# Rariot.net
KiCad netlist of a schematic drawn in EAGLE
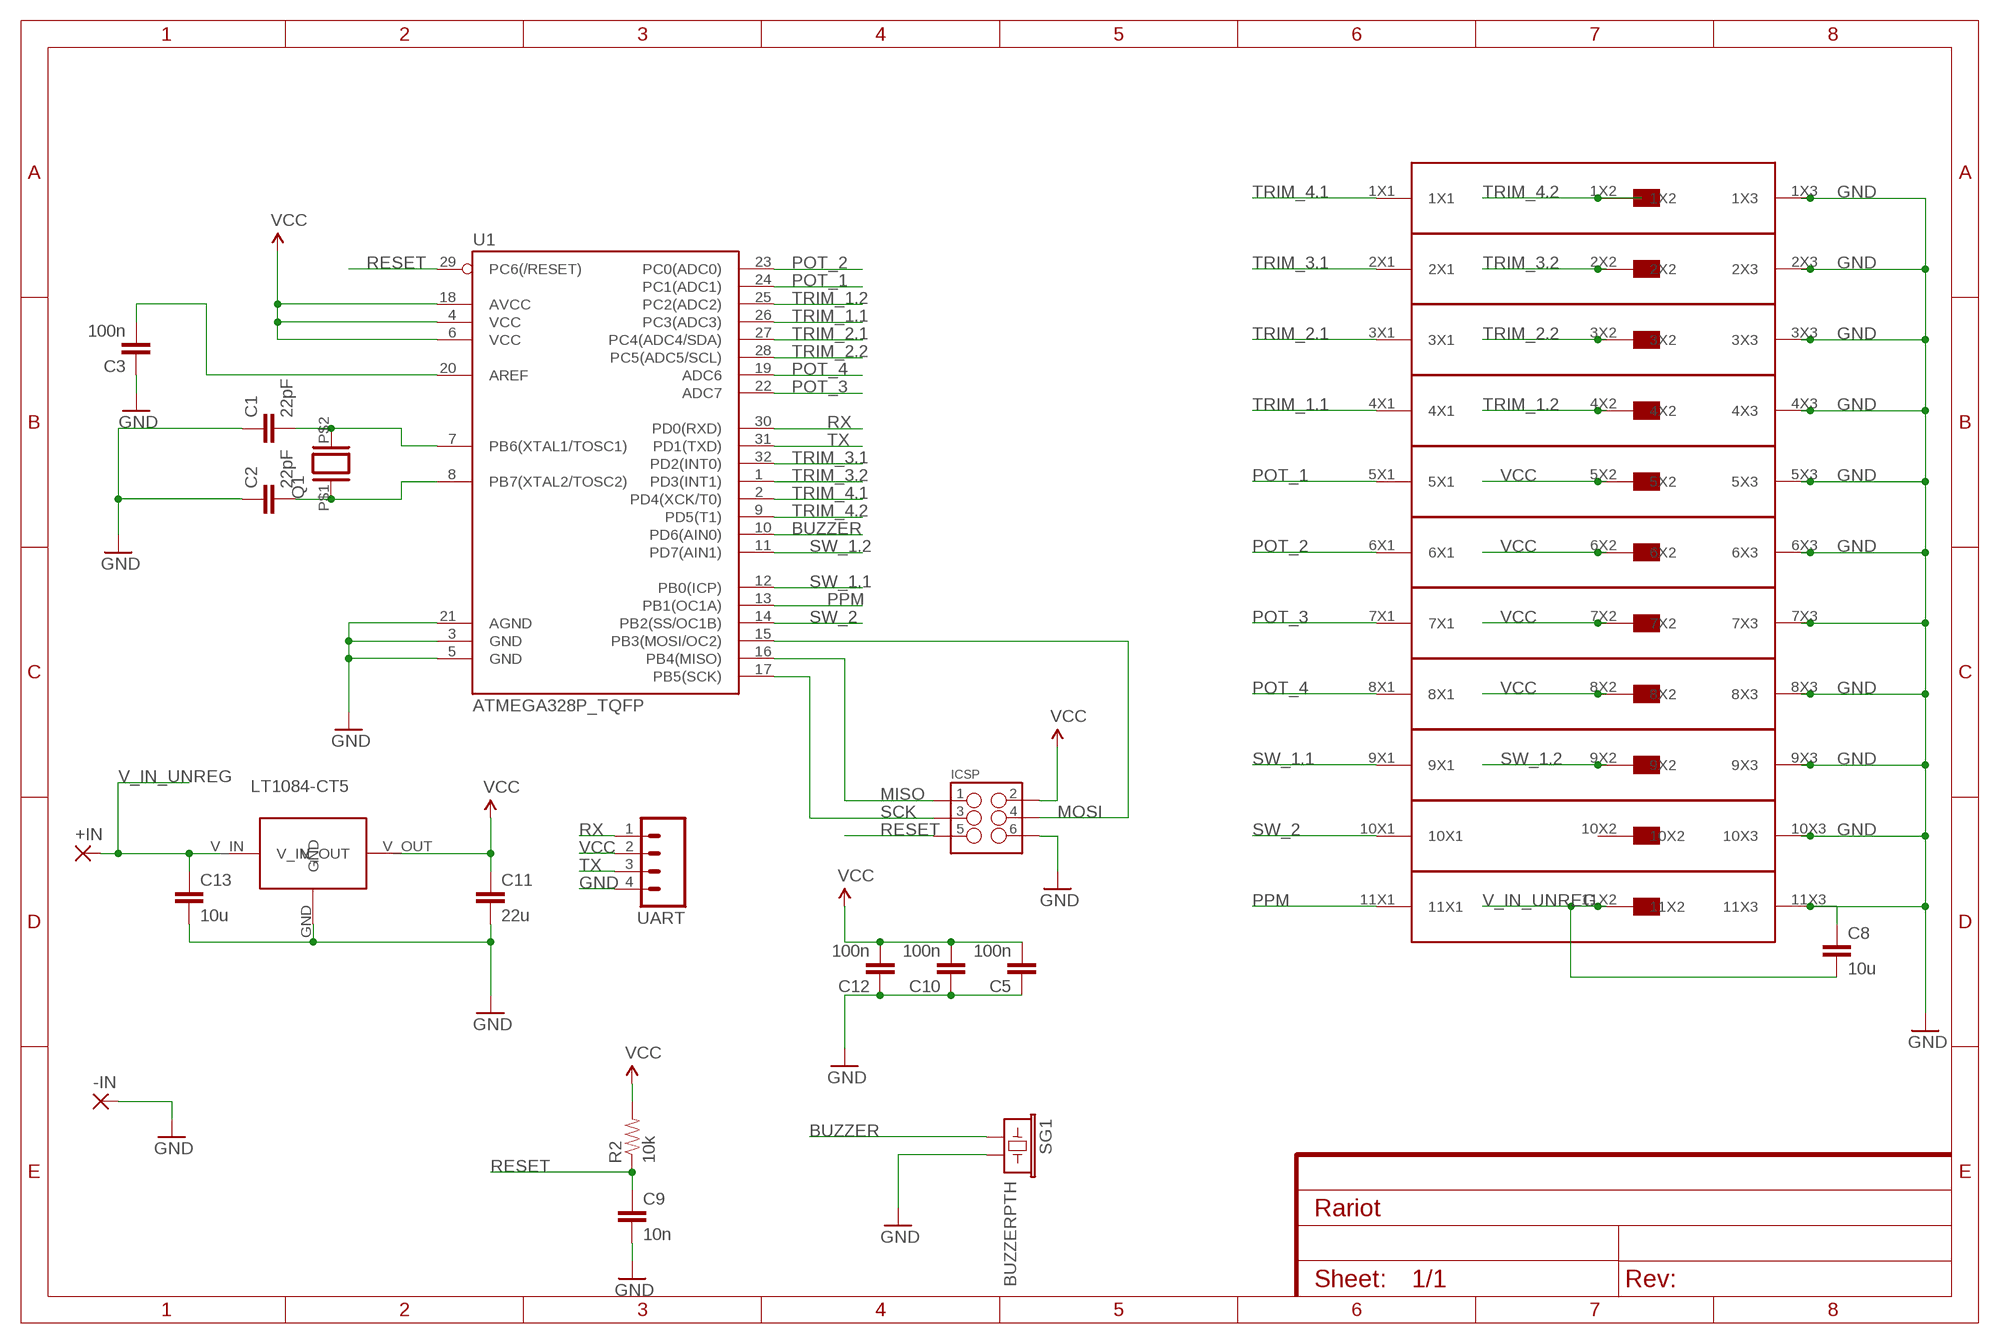
[diagram p0: schematic, sheet 1]

(export (version "E")
  (design (tool "Eeschema 10.0.6"))
  (components
    (comp (ref "+IN")
      (value "SMD5")
      (footprint "eagle-import:SMD2,54-5,08")
      (libsource (lib "eagle-import") (part "SMD5"))
    )
    (comp (ref "-IN")
      (value "SMD5")
      (footprint "eagle-import:SMD2,54-5,08")
      (libsource (lib "eagle-import") (part "SMD5"))
    )
    (comp (ref "C1")
      (value "22pF")
      (footprint "eagle-import:0805")
      (libsource (lib "eagle-import") (part "CAP0805"))
    )
    (comp (ref "C2")
      (value "22pF")
      (footprint "eagle-import:0805")
      (libsource (lib "eagle-import") (part "CAP0805"))
    )
    (comp (ref "C3")
      (value "100n")
      (footprint "eagle-import:0805")
      (libsource (lib "eagle-import") (part "CAP0805"))
    )
    (comp (ref "C5")
      (value "100n")
      (footprint "eagle-import:0805")
      (libsource (lib "eagle-import") (part "CAP0805"))
    )
    (comp (ref "C8")
      (value "10u")
      (footprint "eagle-import:1206")
      (libsource (lib "eagle-import") (part "CAP1206"))
    )
    (comp (ref "C9")
      (value "10n")
      (footprint "eagle-import:0805")
      (libsource (lib "eagle-import") (part "CAP0805"))
    )
    (comp (ref "C10")
      (value "100n")
      (footprint "eagle-import:0805")
      (libsource (lib "eagle-import") (part "CAP0805"))
    )
    (comp (ref "C11")
      (value "22u")
      (footprint "eagle-import:1206")
      (libsource (lib "eagle-import") (part "CAP1206"))
    )
    (comp (ref "C12")
      (value "100n")
      (footprint "eagle-import:0805")
      (libsource (lib "eagle-import") (part "CAP0805"))
    )
    (comp (ref "C13")
      (value "10u")
      (footprint "eagle-import:1206")
      (libsource (lib "eagle-import") (part "CAP1206"))
    )
    (comp (ref "ICSP")
      (value "FEMALE 2x3")
      (footprint "eagle-import:2X3")
      (libsource (lib "eagle-import") (part "M03X2FEMALE"))
    )
    (comp (ref "Q1")
      (value "XTAL/SSMD")
      (footprint "eagle-import:X-TAL_SMD")
      (libsource (lib "eagle-import") (part "XTAL/SSMD"))
    )
    (comp (ref "R2")
      (value "10k")
      (footprint "eagle-import:0805")
      (libsource (lib "eagle-import") (part "RESISTOR0805-RES"))
    )
    (comp (ref "SG1")
      (value "BUZZERPTH")
      (footprint "eagle-import:BUZZER-12MM")
      (libsource (lib "eagle-import") (part "BUZZERPTH"))
    )
    (comp (ref "U$1")
      (value "11X3_2.54_PIN_HEADER")
      (footprint "eagle-import:11X3_2,54_PIN_HEADER")
      (libsource (lib "eagle-import") (part "11X3_2.54_PIN_HEADER"))
    )
    (comp (ref "U$2")
      (value "LT1084-CT5")
      (footprint "eagle-import:TO-220")
      (libsource (lib "eagle-import") (part "LT1084-CT5"))
    )
    (comp (ref "U1")
      (value "ATMEGA328P_TQFP")
      (footprint "eagle-import:TQFP32-08")
      (libsource (lib "eagle-import") (part "ATMEGA328P_TQFP"))
    )
    (comp (ref "UART")
      (value "M04PTH")
      (footprint "eagle-import:1X04")
      (libsource (lib "eagle-import") (part "M04PTH"))
    )
  )
  (nets
    (net (code "1") (name "/BUZZER") (class "Default")
      (node (ref "SG1") (pin "+") (pinfunction "1_+") (pintype "passive"))
      (node (ref "U1") (pin "10") (pinfunction "PD6(AIN0)_10") (pintype "bidirectional"))
    )
    (net (code "2") (name "/MISO") (class "Default")
      (node (ref "ICSP") (pin "1") (pinfunction "1_1") (pintype "bidirectional"))
      (node (ref "U1") (pin "16") (pinfunction "PB4(MISO)_16") (pintype "bidirectional"))
    )
    (net (code "3") (name "/MOSI") (class "Default")
      (node (ref "ICSP") (pin "4") (pinfunction "4_4") (pintype "bidirectional"))
      (node (ref "U1") (pin "15") (pinfunction "PB3(MOSI/OC2)_15") (pintype "bidirectional"))
    )
    (net (code "4") (name "/POT_1") (class "Default")
      (node (ref "U$1") (pin "5X1") (pinfunction "5X1_5X1") (pintype "bidirectional"))
      (node (ref "U1") (pin "24") (pinfunction "PC1(ADC1)_24") (pintype "bidirectional"))
    )
    (net (code "5") (name "/POT_2") (class "Default")
      (node (ref "U$1") (pin "6X1") (pinfunction "6X1_6X1") (pintype "bidirectional"))
      (node (ref "U1") (pin "23") (pinfunction "PC0(ADC0)_23") (pintype "bidirectional"))
    )
    (net (code "6") (name "/POT_3") (class "Default")
      (node (ref "U$1") (pin "7X1") (pinfunction "7X1_7X1") (pintype "bidirectional"))
      (node (ref "U1") (pin "22") (pinfunction "ADC7_22") (pintype "bidirectional"))
    )
    (net (code "7") (name "/POT_4") (class "Default")
      (node (ref "U$1") (pin "8X1") (pinfunction "8X1_8X1") (pintype "bidirectional"))
      (node (ref "U1") (pin "19") (pinfunction "ADC6_19") (pintype "bidirectional"))
    )
    (net (code "8") (name "/PPM") (class "Default")
      (node (ref "U$1") (pin "11X1") (pinfunction "11X1_11X1") (pintype "bidirectional"))
      (node (ref "U1") (pin "13") (pinfunction "PB1(OC1A)_13") (pintype "bidirectional"))
    )
    (net (code "9") (name "/RESET") (class "Default")
      (node (ref "C9") (pin "1") (pinfunction "1_1") (pintype "passive"))
      (node (ref "ICSP") (pin "5") (pinfunction "5_5") (pintype "bidirectional"))
      (node (ref "R2") (pin "1") (pinfunction "1_1") (pintype "passive"))
      (node (ref "U1") (pin "29") (pinfunction "PC6(/RESET)_29") (pintype "bidirectional"))
    )
    (net (code "10") (name "/RX") (class "Default")
      (node (ref "U1") (pin "30") (pinfunction "PD0(RXD)_30") (pintype "bidirectional"))
      (node (ref "UART") (pin "1") (pinfunction "1_1") (pintype "passive"))
    )
    (net (code "11") (name "/SCK") (class "Default")
      (node (ref "ICSP") (pin "3") (pinfunction "3_3") (pintype "bidirectional"))
      (node (ref "U1") (pin "17") (pinfunction "PB5(SCK)_17") (pintype "bidirectional"))
    )
    (net (code "12") (name "/SW_1.1") (class "Default")
      (node (ref "U$1") (pin "9X1") (pinfunction "9X1_9X1") (pintype "bidirectional"))
      (node (ref "U1") (pin "12") (pinfunction "PB0(ICP)_12") (pintype "bidirectional"))
    )
    (net (code "13") (name "/SW_1.2") (class "Default")
      (node (ref "U$1") (pin "9X2") (pinfunction "9X2_9X2") (pintype "bidirectional"))
      (node (ref "U1") (pin "11") (pinfunction "PD7(AIN1)_11") (pintype "bidirectional"))
    )
    (net (code "14") (name "/SW_2") (class "Default")
      (node (ref "U$1") (pin "10X1") (pinfunction "10X1_10X1") (pintype "bidirectional"))
      (node (ref "U1") (pin "14") (pinfunction "PB2(SS/OC1B)_14") (pintype "bidirectional"))
    )
    (net (code "15") (name "/TRIM_1.1") (class "Default")
      (node (ref "U$1") (pin "4X1") (pinfunction "4X1_4X1") (pintype "bidirectional"))
      (node (ref "U1") (pin "26") (pinfunction "PC3(ADC3)_26") (pintype "bidirectional"))
    )
    (net (code "16") (name "/TRIM_1.2") (class "Default")
      (node (ref "U$1") (pin "4X2") (pinfunction "4X2_4X2") (pintype "bidirectional"))
      (node (ref "U1") (pin "25") (pinfunction "PC2(ADC2)_25") (pintype "bidirectional"))
    )
    (net (code "17") (name "/TRIM_2.1") (class "Default")
      (node (ref "U$1") (pin "3X1") (pinfunction "3X1_3X1") (pintype "bidirectional"))
      (node (ref "U1") (pin "27") (pinfunction "PC4(ADC4/SDA)_27") (pintype "bidirectional"))
    )
    (net (code "18") (name "/TRIM_2.2") (class "Default")
      (node (ref "U$1") (pin "3X2") (pinfunction "3X2_3X2") (pintype "bidirectional"))
      (node (ref "U1") (pin "28") (pinfunction "PC5(ADC5/SCL)_28") (pintype "bidirectional"))
    )
    (net (code "19") (name "/TRIM_3.1") (class "Default")
      (node (ref "U$1") (pin "2X1") (pinfunction "2X1_2X1") (pintype "bidirectional"))
      (node (ref "U1") (pin "32") (pinfunction "PD2(INT0)_32") (pintype "bidirectional"))
    )
    (net (code "20") (name "/TRIM_3.2") (class "Default")
      (node (ref "U$1") (pin "2X2") (pinfunction "2X2_2X2") (pintype "bidirectional"))
      (node (ref "U1") (pin "1") (pinfunction "PD3(INT1)_1") (pintype "bidirectional"))
    )
    (net (code "21") (name "/TRIM_4.1") (class "Default")
      (node (ref "U$1") (pin "1X1") (pinfunction "1X1_1X1") (pintype "bidirectional"))
      (node (ref "U1") (pin "2") (pinfunction "PD4(XCK/T0)_2") (pintype "bidirectional"))
    )
    (net (code "22") (name "/TRIM_4.2") (class "Default")
      (node (ref "U$1") (pin "1X2") (pinfunction "1X2_1X2") (pintype "bidirectional"))
      (node (ref "U1") (pin "9") (pinfunction "PD5(T1)_9") (pintype "bidirectional"))
    )
    (net (code "23") (name "/TX") (class "Default")
      (node (ref "U1") (pin "31") (pinfunction "PD1(TXD)_31") (pintype "bidirectional"))
      (node (ref "UART") (pin "3") (pinfunction "3_3") (pintype "passive"))
    )
    (net (code "24") (name "/V_IN_UNREG") (class "Default")
      (node (ref "+IN") (pin "1") (pinfunction "P_1") (pintype "passive"))
      (node (ref "C13") (pin "1") (pinfunction "1_1") (pintype "passive"))
      (node (ref "C8") (pin "2") (pinfunction "2_2") (pintype "passive"))
      (node (ref "U$1") (pin "11X2") (pinfunction "11X2_11X2") (pintype "bidirectional"))
      (node (ref "U$2") (pin "V_IN") (pinfunction "V_IN_V_IN") (pintype "bidirectional"))
    )
    (net (code "25") (name "GND") (class "Default")
      (node (ref "-IN") (pin "1") (pinfunction "P_1") (pintype "passive"))
      (node (ref "C1") (pin "1") (pinfunction "1_1") (pintype "passive"))
      (node (ref "C10") (pin "1") (pinfunction "1_1") (pintype "passive"))
      (node (ref "C11") (pin "2") (pinfunction "2_2") (pintype "passive"))
      (node (ref "C12") (pin "1") (pinfunction "1_1") (pintype "passive"))
      (node (ref "C13") (pin "2") (pinfunction "2_2") (pintype "passive"))
      (node (ref "C2") (pin "1") (pinfunction "1_1") (pintype "passive"))
      (node (ref "C3") (pin "1") (pinfunction "1_1") (pintype "passive"))
      (node (ref "C5") (pin "1") (pinfunction "1_1") (pintype "passive"))
      (node (ref "C8") (pin "1") (pinfunction "1_1") (pintype "passive"))
      (node (ref "C9") (pin "2") (pinfunction "2_2") (pintype "passive"))
      (node (ref "ICSP") (pin "6") (pinfunction "6_6") (pintype "bidirectional"))
      (node (ref "SG1") (pin "-") (pinfunction "2_-") (pintype "passive"))
      (node (ref "U$1") (pin "10X3") (pinfunction "10X3_10X3") (pintype "bidirectional"))
      (node (ref "U$1") (pin "11X3") (pinfunction "11X3_11X3") (pintype "bidirectional"))
      (node (ref "U$1") (pin "1X3") (pinfunction "1X3_1X3") (pintype "bidirectional"))
      (node (ref "U$1") (pin "2X3") (pinfunction "2X3_2X3") (pintype "bidirectional"))
      (node (ref "U$1") (pin "3X3") (pinfunction "3X3_3X3") (pintype "bidirectional"))
      (node (ref "U$1") (pin "4X3") (pinfunction "4X3_4X3") (pintype "bidirectional"))
      (node (ref "U$1") (pin "5X3") (pinfunction "5X3_5X3") (pintype "bidirectional"))
      (node (ref "U$1") (pin "6X3") (pinfunction "6X3_6X3") (pintype "bidirectional"))
      (node (ref "U$1") (pin "7X3") (pinfunction "7X3_7X3") (pintype "bidirectional"))
      (node (ref "U$1") (pin "8X3") (pinfunction "8X3_8X3") (pintype "bidirectional"))
      (node (ref "U$1") (pin "9X3") (pinfunction "9X3_9X3") (pintype "bidirectional"))
      (node (ref "U$2") (pin "GND") (pinfunction "GND_GND") (pintype "bidirectional"))
      (node (ref "U1") (pin "21") (pinfunction "AGND_21") (pintype "bidirectional"))
      (node (ref "U1") (pin "3") (pinfunction "GND_3") (pintype "bidirectional"))
      (node (ref "U1") (pin "5") (pinfunction "GND_5") (pintype "bidirectional"))
      (node (ref "UART") (pin "4") (pinfunction "4_4") (pintype "passive"))
    )
    (net (code "26") (name "Net-(Q1-1)") (class "Default")
      (node (ref "C2") (pin "2") (pinfunction "2_2") (pintype "passive"))
      (node (ref "Q1") (pin "P$1") (pinfunction "1_P$1") (pintype "passive"))
      (node (ref "U1") (pin "8") (pinfunction "PB7(XTAL2/TOSC2)_8") (pintype "bidirectional"))
    )
    (net (code "27") (name "Net-(Q1-2)") (class "Default")
      (node (ref "C1") (pin "2") (pinfunction "2_2") (pintype "passive"))
      (node (ref "Q1") (pin "P$2") (pinfunction "2_P$2") (pintype "passive"))
      (node (ref "U1") (pin "7") (pinfunction "PB6(XTAL1/TOSC1)_7") (pintype "bidirectional"))
    )
    (net (code "28") (name "Net-(U1-AREF)") (class "Default")
      (node (ref "C3") (pin "2") (pinfunction "2_2") (pintype "passive"))
      (node (ref "U1") (pin "20") (pinfunction "AREF_20") (pintype "bidirectional"))
    )
    (net (code "29") (name "VCC") (class "Default")
      (node (ref "C10") (pin "2") (pinfunction "2_2") (pintype "passive"))
      (node (ref "C11") (pin "1") (pinfunction "1_1") (pintype "passive"))
      (node (ref "C12") (pin "2") (pinfunction "2_2") (pintype "passive"))
      (node (ref "C5") (pin "2") (pinfunction "2_2") (pintype "passive"))
      (node (ref "ICSP") (pin "2") (pinfunction "2_2") (pintype "bidirectional"))
      (node (ref "R2") (pin "2") (pinfunction "2_2") (pintype "passive"))
      (node (ref "U$1") (pin "5X2") (pinfunction "5X2_5X2") (pintype "bidirectional"))
      (node (ref "U$1") (pin "6X2") (pinfunction "6X2_6X2") (pintype "bidirectional"))
      (node (ref "U$1") (pin "7X2") (pinfunction "7X2_7X2") (pintype "bidirectional"))
      (node (ref "U$1") (pin "8X2") (pinfunction "8X2_8X2") (pintype "bidirectional"))
      (node (ref "U$2") (pin "V_OUT") (pinfunction "V_OUT_V_OUT") (pintype "bidirectional"))
      (node (ref "U1") (pin "18") (pinfunction "AVCC_18") (pintype "bidirectional"))
      (node (ref "U1") (pin "4") (pinfunction "VCC_4") (pintype "bidirectional"))
      (node (ref "U1") (pin "6") (pinfunction "VCC_6") (pintype "bidirectional"))
      (node (ref "UART") (pin "2") (pinfunction "2_2") (pintype "passive"))
    )
    (net (code "30") (name "unconnected-(U$1-Pad10X2)") (class "Default")
      (node (ref "U$1") (pin "10X2") (pinfunction "10X2_10X2") (pintype "bidirectional"))
    )
  )
)
